# UVC_Module.net
KiCad netlist of a schematic drawn in EAGLE
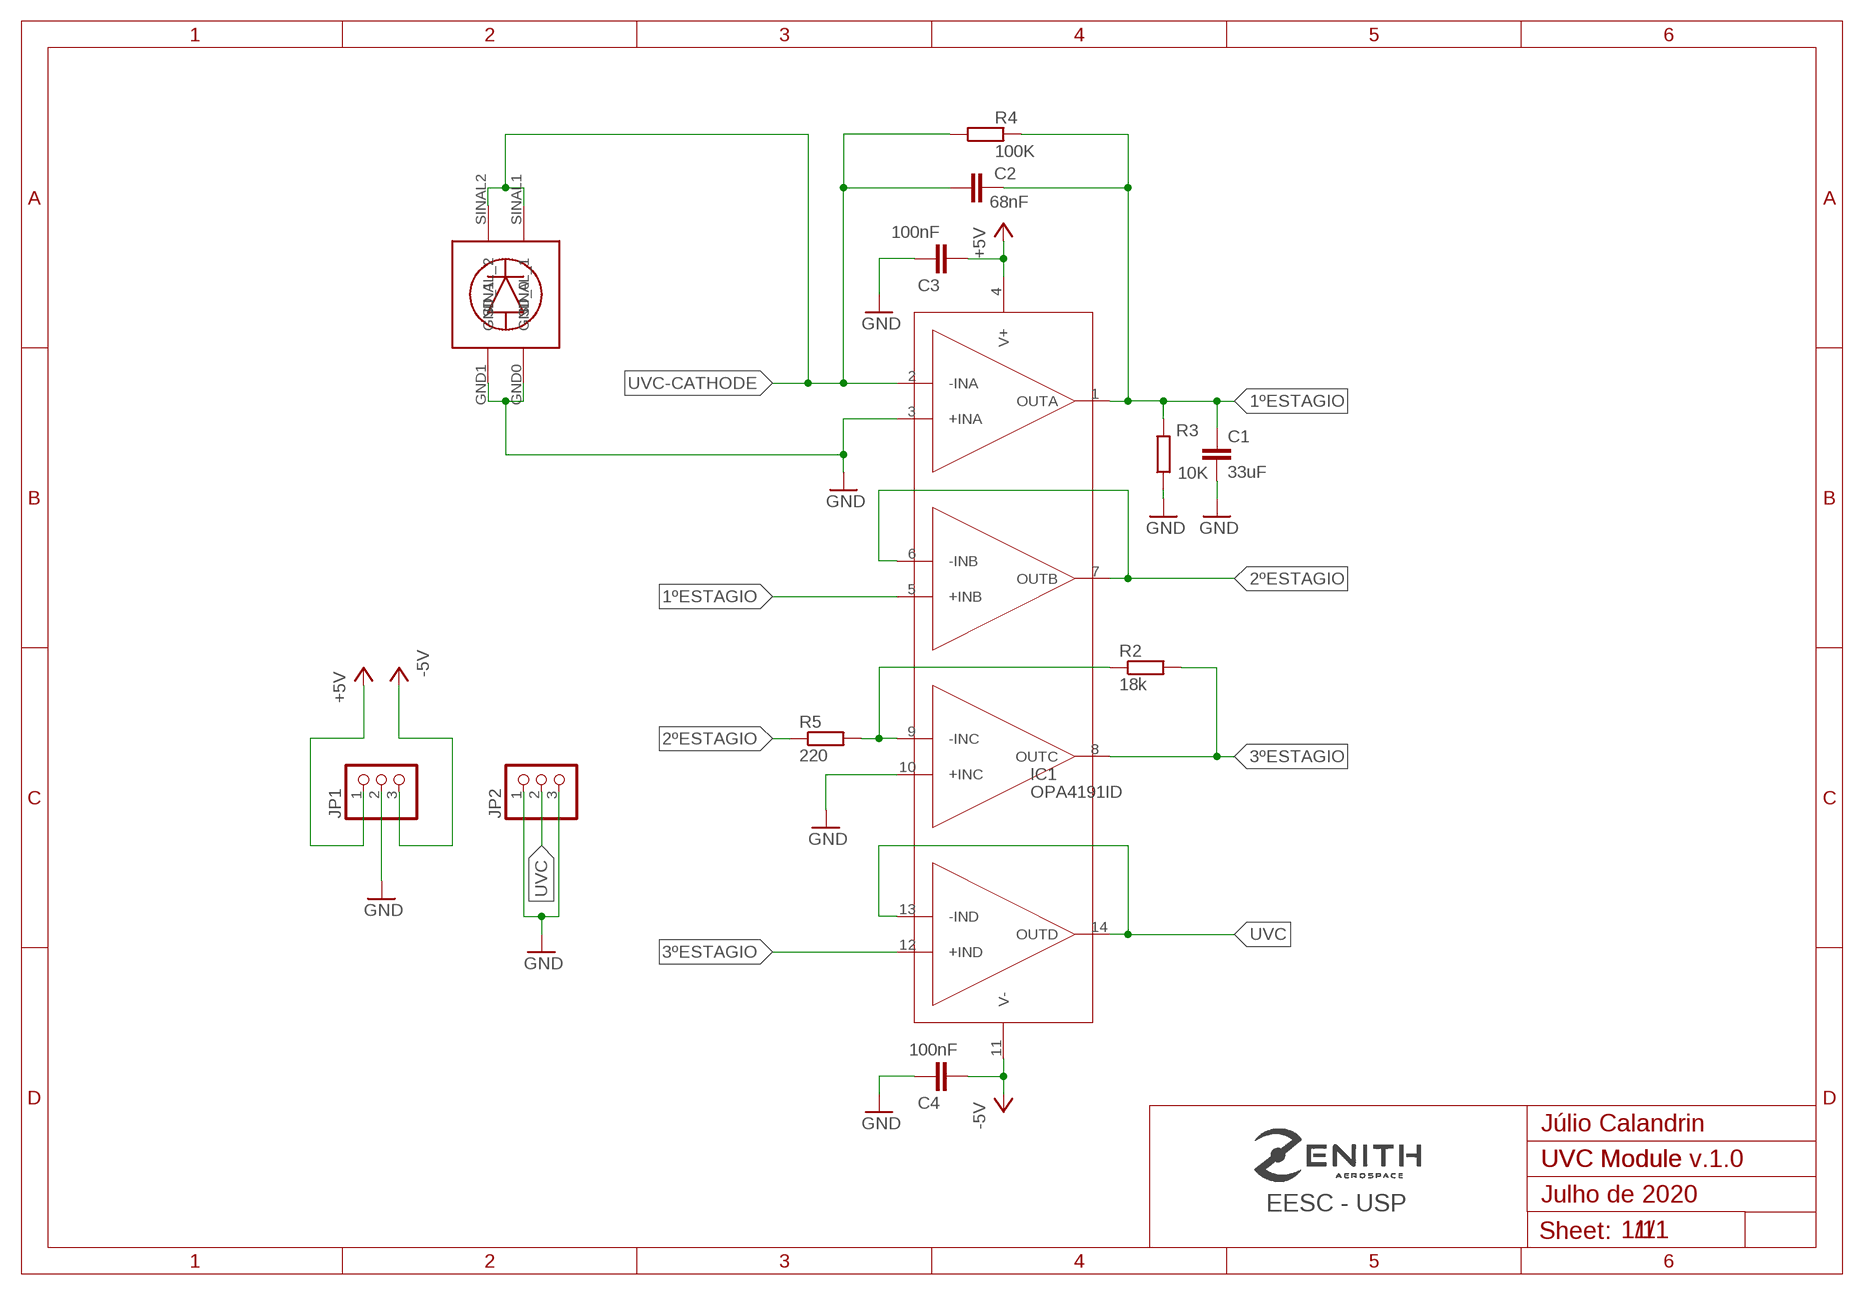
[diagram p0: schematic, sheet 1]

(export (version "E")
  (design (tool "Eeschema 10.0.6"))
  (components
    (comp (ref "C1")
      (value "33uF")
      (footprint "eagle-import:C0805")
      (libsource (lib "eagle-import") (part "C-EUC0805"))
    )
    (comp (ref "C2")
      (value "68nF")
      (footprint "eagle-import:C0805")
      (libsource (lib "eagle-import") (part "C-EUC0805"))
    )
    (comp (ref "C3")
      (value "100nF")
      (footprint "eagle-import:C0805")
      (libsource (lib "eagle-import") (part "C-EUC0805"))
    )
    (comp (ref "C4")
      (value "100nF")
      (footprint "eagle-import:C0805")
      (libsource (lib "eagle-import") (part "C-EUC0805"))
    )
    (comp (ref "IC1")
      (value "OPA4191ID")
      (footprint "eagle-import:D14_TEX")
      (fields (field (name "COPYRIGHT") "Copyright (C) 2018 Accelerated Designs. All rights reserved"))
      (libsource (lib "eagle-import") (part "OPA4191ID"))
    )
    (comp (ref "JP1")
      (value "PINHD-1X3")
      (footprint "eagle-import:1X03")
      (libsource (lib "eagle-import") (part "PINHD-1X3"))
    )
    (comp (ref "JP2")
      (value "PINHD-1X3")
      (footprint "eagle-import:1X03")
      (libsource (lib "eagle-import") (part "PINHD-1X3"))
    )
    (comp (ref "R2")
      (value "18k")
      (footprint "eagle-import:R0805")
      (libsource (lib "eagle-import") (part "R-EU_R0805"))
    )
    (comp (ref "R3")
      (value "10K")
      (footprint "eagle-import:R0805")
      (libsource (lib "eagle-import") (part "R-EU_R0805"))
    )
    (comp (ref "R4")
      (value "100K")
      (footprint "eagle-import:R0805")
      (libsource (lib "eagle-import") (part "R-EU_R0805"))
    )
    (comp (ref "R5")
      (value "220")
      (footprint "eagle-import:R0805")
      (libsource (lib "eagle-import") (part "R-EU_R0805"))
    )
    (comp (ref "U$1")
      (value "BREAKOUT_UV-C")
      (footprint "eagle-import:PADS_UV-C")
      (libsource (lib "eagle-import") (part "BREAKOUT_UV-C"))
    )
  )
  (nets
    (net (code "1") (name "+5V") (class "Default")
      (node (ref "C3") (pin "1") (pinfunction "1_1") (pintype "passive"))
      (node (ref "IC1") (pin "4") (pinfunction "V+_4") (pintype "power_in"))
      (node (ref "JP1") (pin "1") (pinfunction "1_1") (pintype "passive"))
    )
    (net (code "2") (name "-5V") (class "Default")
      (node (ref "C4") (pin "1") (pinfunction "1_1") (pintype "passive"))
      (node (ref "IC1") (pin "11") (pinfunction "V-_11") (pintype "power_in"))
      (node (ref "JP1") (pin "3") (pinfunction "3_3") (pintype "passive"))
    )
    (net (code "3") (name "1ºESTAGIO") (class "Default")
      (node (ref "C1") (pin "1") (pinfunction "1_1") (pintype "passive"))
      (node (ref "C2") (pin "2") (pinfunction "2_2") (pintype "passive"))
      (node (ref "IC1") (pin "1") (pinfunction "OUTA_1") (pintype "output"))
      (node (ref "IC1") (pin "5") (pinfunction "+INB_5") (pintype "input"))
      (node (ref "R3") (pin "2") (pinfunction "2_2") (pintype "passive"))
      (node (ref "R4") (pin "2") (pinfunction "2_2") (pintype "passive"))
    )
    (net (code "4") (name "2ºESTAGIO") (class "Default")
      (node (ref "IC1") (pin "6") (pinfunction "-INB_6") (pintype "passive"))
      (node (ref "IC1") (pin "7") (pinfunction "OUTB_7") (pintype "output"))
      (node (ref "R5") (pin "1") (pinfunction "1_1") (pintype "passive"))
    )
    (net (code "5") (name "3ºESTAGIO") (class "Default")
      (node (ref "IC1") (pin "12") (pinfunction "+IND_12") (pintype "input"))
      (node (ref "IC1") (pin "8") (pinfunction "OUTC_8") (pintype "output"))
      (node (ref "R2") (pin "2") (pinfunction "2_2") (pintype "passive"))
    )
    (net (code "6") (name "GND") (class "Default")
      (node (ref "C1") (pin "2") (pinfunction "2_2") (pintype "passive"))
      (node (ref "C3") (pin "2") (pinfunction "2_2") (pintype "passive"))
      (node (ref "C4") (pin "2") (pinfunction "2_2") (pintype "passive"))
      (node (ref "IC1") (pin "10") (pinfunction "+INC_10") (pintype "input"))
      (node (ref "IC1") (pin "3") (pinfunction "+INA_3") (pintype "input"))
      (node (ref "JP1") (pin "2") (pinfunction "2_2") (pintype "passive"))
      (node (ref "JP2") (pin "1") (pinfunction "1_1") (pintype "passive"))
      (node (ref "JP2") (pin "3") (pinfunction "3_3") (pintype "passive"))
      (node (ref "R3") (pin "1") (pinfunction "1_1") (pintype "passive"))
      (node (ref "U$1") (pin "GND0") (pinfunction "GND_0_GND0") (pintype "bidirectional"))
      (node (ref "U$1") (pin "GND1") (pinfunction "GND_1_GND1") (pintype "bidirectional"))
    )
    (net (code "7") (name "Net-(IC1--INC)") (class "Default")
      (node (ref "IC1") (pin "9") (pinfunction "-INC_9") (pintype "input"))
      (node (ref "R2") (pin "1") (pinfunction "1_1") (pintype "passive"))
      (node (ref "R5") (pin "2") (pinfunction "2_2") (pintype "passive"))
    )
    (net (code "8") (name "UVC") (class "Default")
      (node (ref "IC1") (pin "13") (pinfunction "-IND_13") (pintype "input"))
      (node (ref "IC1") (pin "14") (pinfunction "OUTD_14") (pintype "output"))
      (node (ref "JP2") (pin "2") (pinfunction "2_2") (pintype "passive"))
    )
    (net (code "9") (name "UVC-CATHODE") (class "Default")
      (node (ref "C2") (pin "1") (pinfunction "1_1") (pintype "passive"))
      (node (ref "IC1") (pin "2") (pinfunction "-INA_2") (pintype "passive"))
      (node (ref "R4") (pin "1") (pinfunction "1_1") (pintype "passive"))
      (node (ref "U$1") (pin "SINAL1") (pinfunction "SINAL_1_SINAL1") (pintype "bidirectional"))
      (node (ref "U$1") (pin "SINAL2") (pinfunction "SINAL_2_SINAL2") (pintype "bidirectional"))
    )
  )
)
